# airball_sensor_board_v8_fwd.net
KiCad netlist of a schematic drawn in EAGLE
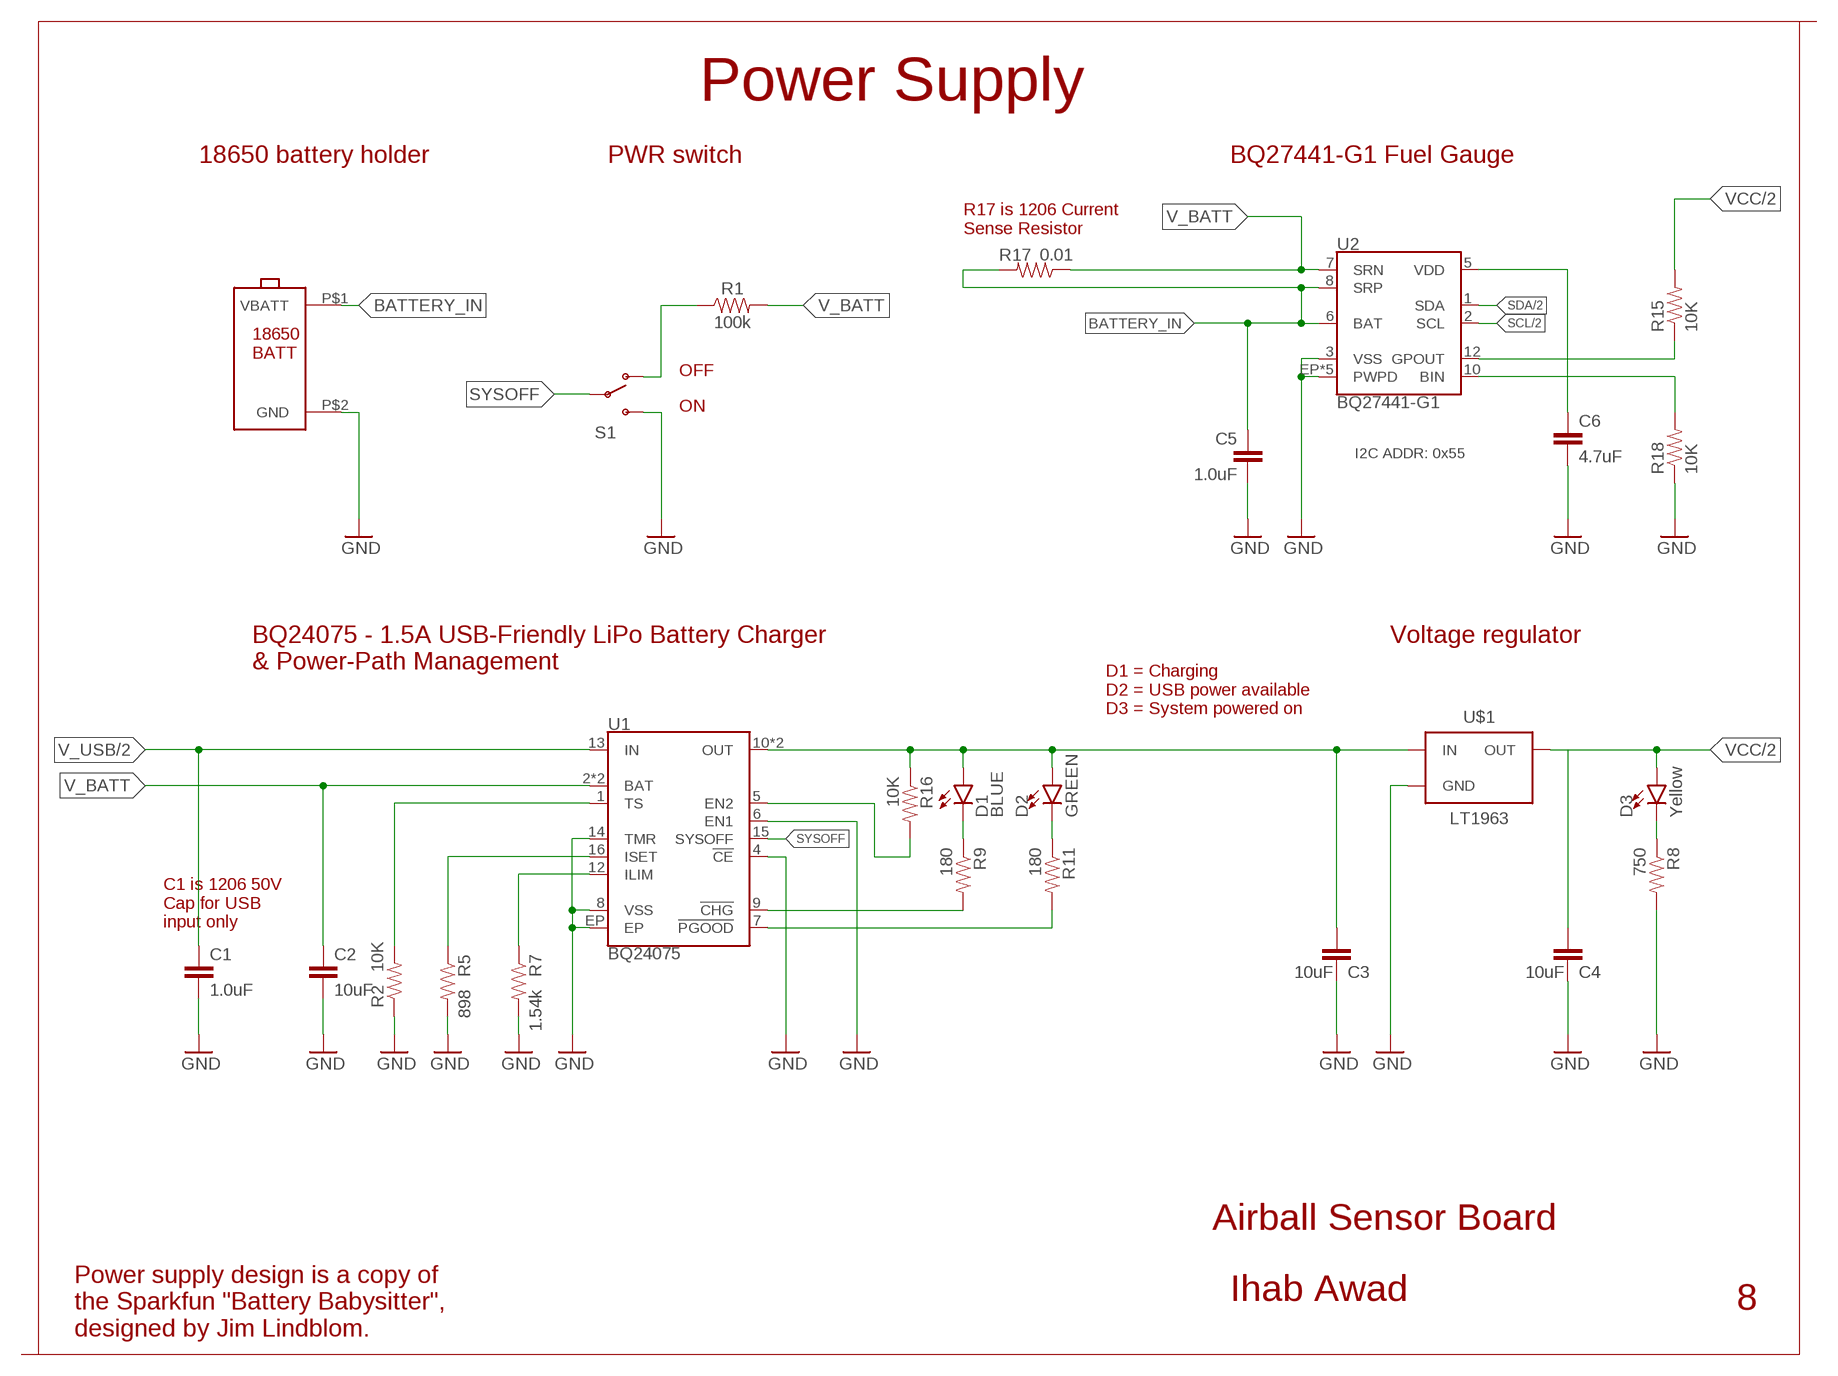
[diagram p0: schematic, sheet 1]
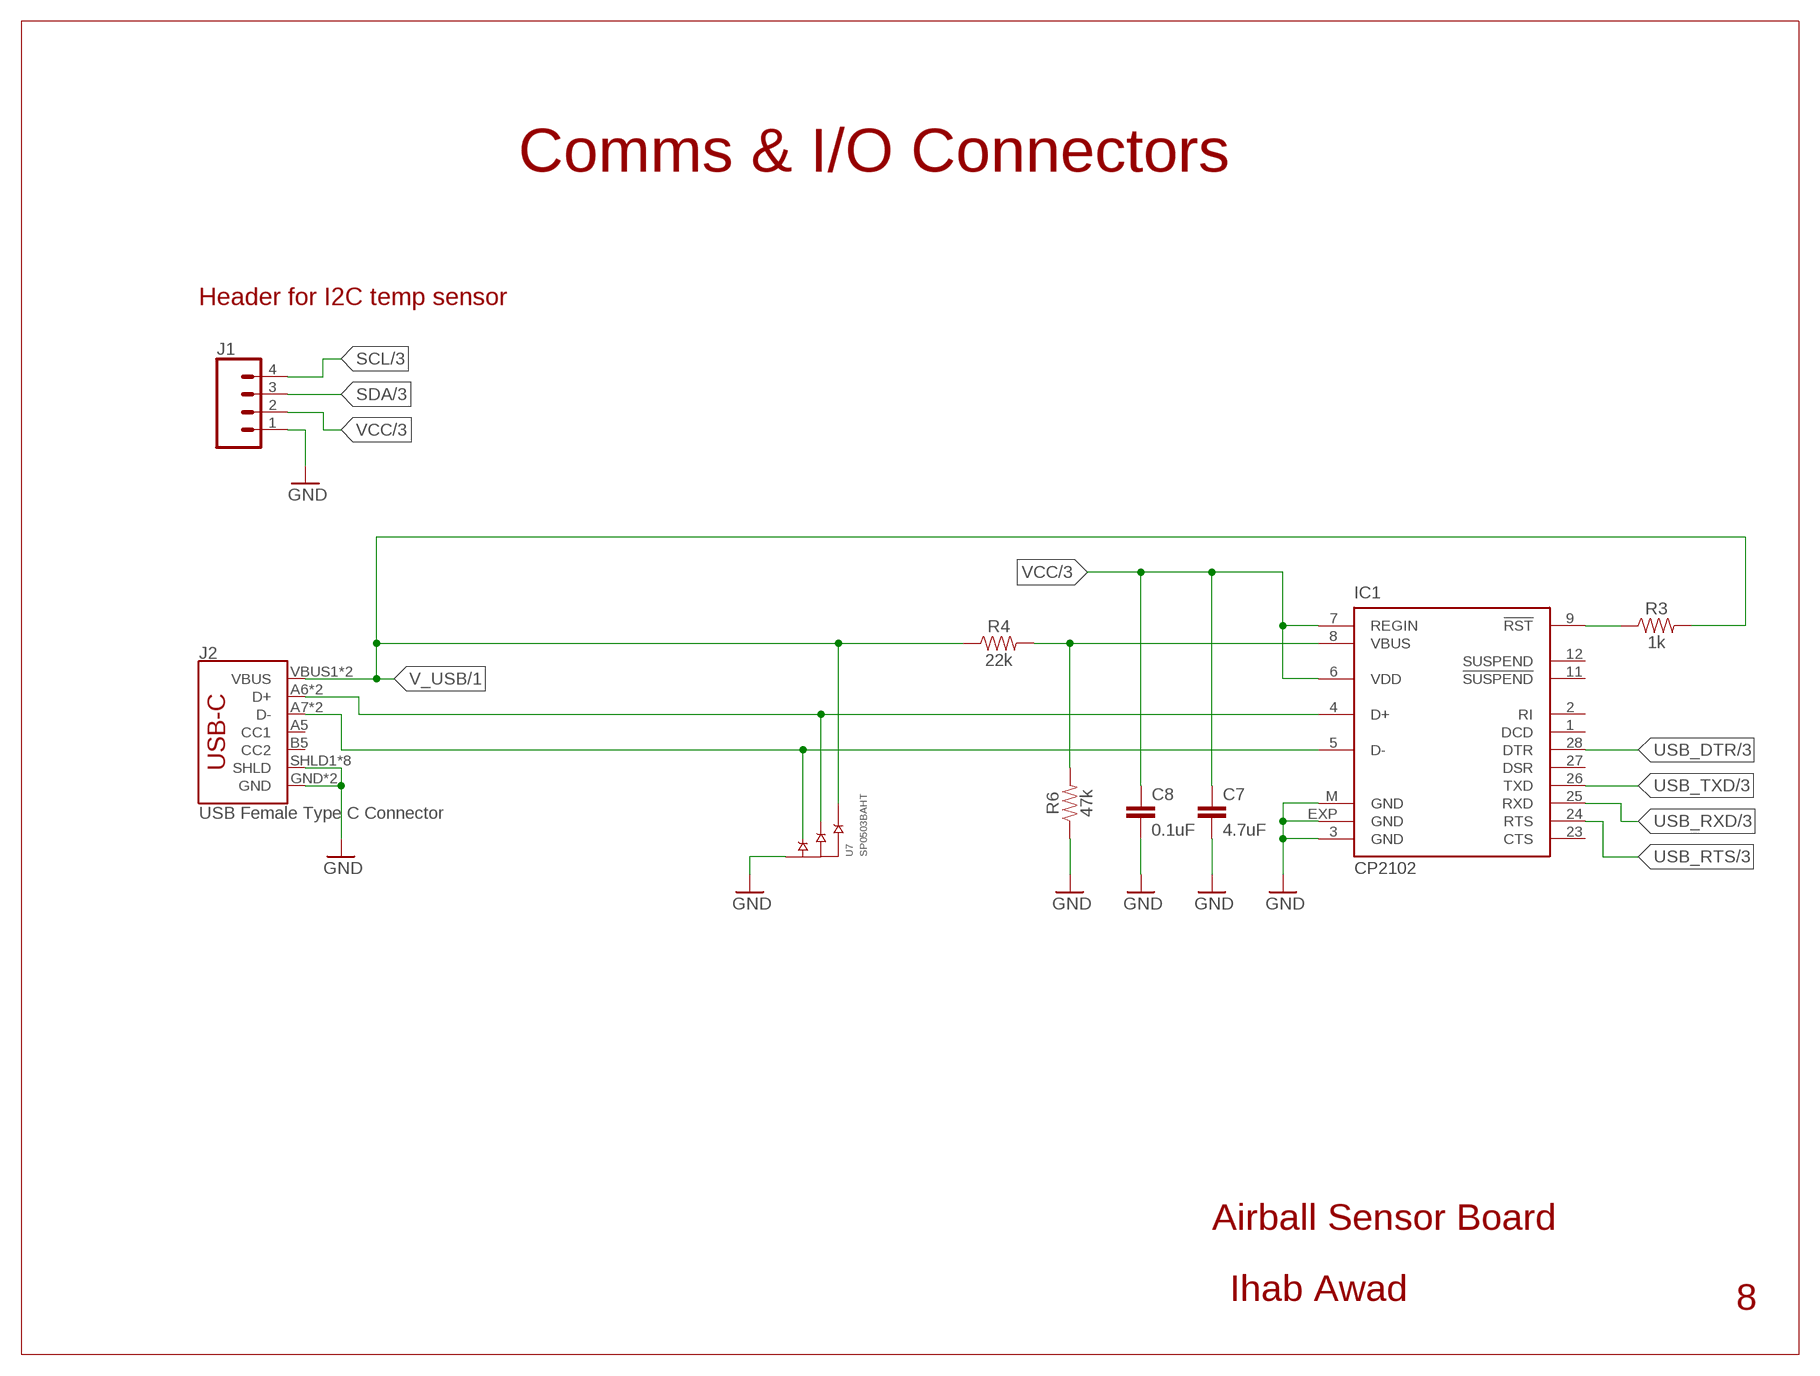
[diagram p1: schematic, sheet 2]
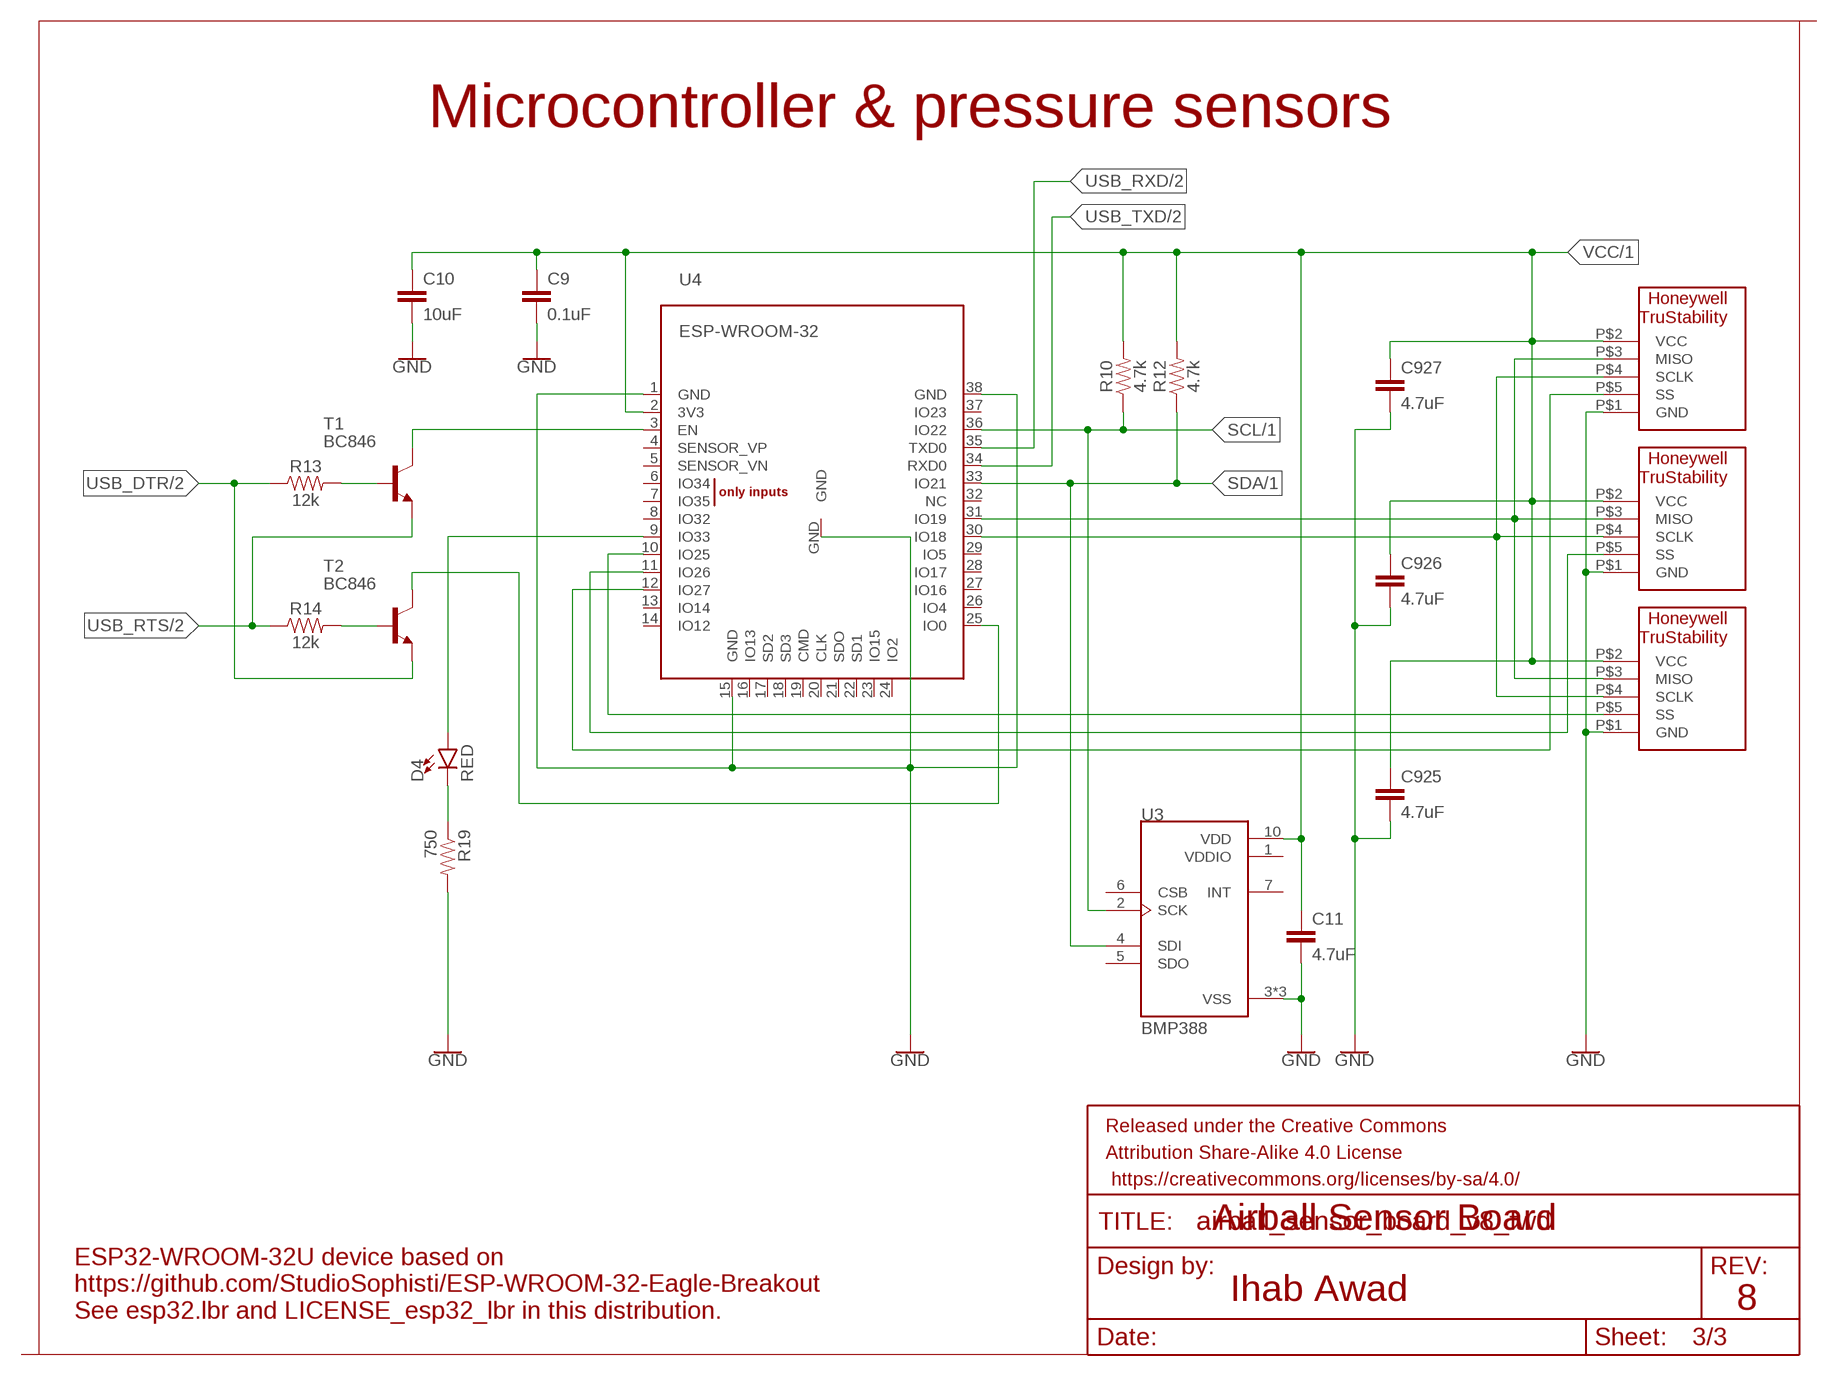
[diagram p2: schematic, sheet 3]

(export (version "E")
  (design (tool "Eeschema 10.0.6"))
  (components
    (comp (ref "C9")
      (value "0.1uF")
      (footprint "eagle-import:0603")
      (libsource (lib "eagle-import") (part "0.1UF-0603-25V-(+80/-20%)"))
    )
    (comp (ref "C10")
      (value "10uF")
      (footprint "eagle-import:0603")
      (libsource (lib "eagle-import") (part "10UF-0603-6.3V-20%"))
    )
    (comp (ref "C11")
      (value "4.7uF")
      (footprint "eagle-import:0603")
      (libsource (lib "eagle-import") (part "4.7UF-0603-6.3V-(10%)"))
    )
    (comp (ref "C925")
      (value "4.7uF")
      (footprint "eagle-import:0603")
      (libsource (lib "eagle-import") (part "4.7UF-0603-6.3V-(10%)"))
    )
    (comp (ref "C926")
      (value "4.7uF")
      (footprint "eagle-import:0603")
      (libsource (lib "eagle-import") (part "4.7UF-0603-6.3V-(10%)"))
    )
    (comp (ref "C927")
      (value "4.7uF")
      (footprint "eagle-import:0603")
      (libsource (lib "eagle-import") (part "4.7UF-0603-6.3V-(10%)"))
    )
    (comp (ref "D4")
      (value "RED")
      (footprint "eagle-import:LED-0603")
      (libsource (lib "eagle-import") (part "LED-RED0603"))
    )
    (comp (ref "FRAME3")
      (value "FRAME-LETTER")
      (footprint "eagle-import:CREATIVE_COMMONS")
      (libsource (lib "eagle-import") (part "FRAME-LETTER"))
    )
    (comp (ref "R10")
      (value "4.7k")
      (footprint "eagle-import:0603")
      (libsource (lib "eagle-import") (part "4.7KOHM-0603-1/10W-1%"))
    )
    (comp (ref "R12")
      (value "4.7k")
      (footprint "eagle-import:0603")
      (libsource (lib "eagle-import") (part "4.7KOHM-0603-1/10W-1%"))
    )
    (comp (ref "R13")
      (value "12k")
      (footprint "eagle-import:0603")
      (libsource (lib "eagle-import") (part "12KOHM-0603-1/10W-1%"))
    )
    (comp (ref "R14")
      (value "12k")
      (footprint "eagle-import:0603")
      (libsource (lib "eagle-import") (part "12KOHM-0603-1/10W-1%"))
    )
    (comp (ref "R19")
      (value "750")
      (footprint "eagle-import:0603-RES")
      (libsource (lib "eagle-import") (part "10KOHM-1/10W-1%(0603)0603"))
    )
    (comp (ref "T1")
      (value "BC846")
      (footprint "eagle-import:SOT23")
      (libsource (lib "eagle-import") (part "BC846"))
    )
    (comp (ref "T2")
      (value "BC846")
      (footprint "eagle-import:SOT23")
      (libsource (lib "eagle-import") (part "BC846"))
    )
    (comp (ref "U$925")
      (value "HONEYWELL_HSC_SMT")
      (footprint "eagle-import:HONEYWELL_HSC_SMT")
      (libsource (lib "eagle-import") (part "HONEYWELL_HSC_SMT"))
    )
    (comp (ref "U$926")
      (value "HONEYWELL_HSC_SMT")
      (footprint "eagle-import:HONEYWELL_HSC_SMT")
      (libsource (lib "eagle-import") (part "HONEYWELL_HSC_SMT"))
    )
    (comp (ref "U$927")
      (value "HONEYWELL_HSC_SMT")
      (footprint "eagle-import:HONEYWELL_HSC_SMT")
      (libsource (lib "eagle-import") (part "HONEYWELL_HSC_SMT"))
    )
    (comp (ref "U3")
      (value "BMP388")
      (footprint "eagle-import:PQFN50P200X200X80-10N")
      (fields (field (name "MF") "Bosch Sensortec"))
      (libsource (lib "eagle-import") (part "BMP388"))
    )
    (comp (ref "U4")
      (value "ESP-WROOM-32")
      (footprint "eagle-import:ESP-WROOM-32")
      (libsource (lib "eagle-import") (part "ESP-WROOM-32"))
    )
    (comp (ref "C7")
      (value "4.7uF")
      (footprint "eagle-import:0603")
      (libsource (lib "eagle-import") (part "4.7UF-0603-35V-(20%)"))
    )
    (comp (ref "C8")
      (value "0.1uF")
      (footprint "eagle-import:0603")
      (libsource (lib "eagle-import") (part "0.1UF-0603-25V-(+80/-20%)"))
    )
    (comp (ref "IC1")
      (value "CP2102")
      (footprint "eagle-import:MLP28")
      (fields (field (name "MF") "FARNELL") (field (name "MPN") "CP2102-GM"))
      (libsource (lib "eagle-import") (part "CP2102"))
    )
    (comp (ref "J1")
      (value "CONN_04JST-PTH")
      (footprint "eagle-import:JST-4-PTH")
      (libsource (lib "eagle-import") (part "CONN_04JST-PTH"))
    )
    (comp (ref "J2")
      (value "USB Female Type C Connector")
      (footprint "eagle-import:USB-C-16P")
      (libsource (lib "eagle-import") (part "USB_C"))
    )
    (comp (ref "R3")
      (value "1k")
      (footprint "eagle-import:0603")
      (libsource (lib "eagle-import") (part "1KOHM-0603-1/10W-1%"))
    )
    (comp (ref "R4")
      (value "22k")
      (footprint "eagle-import:0603")
      (libsource (lib "eagle-import") (part "22KOHM-0603-1/10W-1%"))
    )
    (comp (ref "R6")
      (value "47k")
      (footprint "eagle-import:0603")
      (libsource (lib "eagle-import") (part "47KOHM-0603-1/10W-1%"))
    )
    (comp (ref "U7")
      (value "SP0503BAHT")
      (footprint "eagle-import:SOT143")
      (fields (field (name "DIGI-KEY_PART_NUMBER") "F2715TR-ND") (field (name "MF") "Littelfuse Inc."))
      (libsource (lib "eagle-import") (part "SP0503BAHT"))
    )
    (comp (ref "C1")
      (value "1.0uF")
      (footprint "eagle-import:1206-CAP")
      (libsource (lib "eagle-import") (part "1.0UF50V10%(1206)"))
    )
    (comp (ref "C2")
      (value "10uF")
      (footprint "eagle-import:0805-CAP")
      (libsource (lib "eagle-import") (part "10UF10V10%(0805)"))
    )
    (comp (ref "C3")
      (value "10uF")
      (footprint "eagle-import:0805-CAP")
      (libsource (lib "eagle-import") (part "10UF10V10%(0805)"))
    )
    (comp (ref "C4")
      (value "10uF")
      (footprint "eagle-import:0805-CAP")
      (libsource (lib "eagle-import") (part "10UF10V10%(0805)"))
    )
    (comp (ref "C5")
      (value "1.0uF")
      (footprint "eagle-import:0603-CAP")
      (libsource (lib "eagle-import") (part "1.0UF-16V-10%(0603)"))
    )
    (comp (ref "C6")
      (value "4.7uF")
      (footprint "eagle-import:0603")
      (libsource (lib "eagle-import") (part "4.7UF-0603-35V-(20%)"))
    )
    (comp (ref "D1")
      (value "BLUE")
      (footprint "eagle-import:LED-0603")
      (libsource (lib "eagle-import") (part "LED-BLUE0603"))
    )
    (comp (ref "D2")
      (value "GREEN")
      (footprint "eagle-import:LED-0603")
      (libsource (lib "eagle-import") (part "LED-GREEN0603"))
    )
    (comp (ref "D3")
      (value "Yellow")
      (footprint "eagle-import:LED-0603")
      (libsource (lib "eagle-import") (part "LED-YELLOW0603"))
    )
    (comp (ref "R1")
      (value "100k")
      (footprint "eagle-import:0603")
      (libsource (lib "eagle-import") (part "100KOHM-0603-1/10W-1%"))
    )
    (comp (ref "R2")
      (value "10K")
      (footprint "eagle-import:0603-RES")
      (libsource (lib "eagle-import") (part "10KOHM-1/10W-1%(0603)0603"))
    )
    (comp (ref "R5")
      (value "898")
      (footprint "eagle-import:0603-RES")
      (libsource (lib "eagle-import") (part "RESISTOR0603-RES"))
    )
    (comp (ref "R7")
      (value "1.54k")
      (footprint "eagle-import:0603-RES")
      (libsource (lib "eagle-import") (part "RESISTOR0603-RES"))
    )
    (comp (ref "R8")
      (value "750")
      (footprint "eagle-import:0603-RES")
      (libsource (lib "eagle-import") (part "10KOHM-1/10W-1%(0603)0603"))
    )
    (comp (ref "R9")
      (value "180")
      (footprint "eagle-import:0603-RES")
      (libsource (lib "eagle-import") (part "180OHM1/10W1%(0603)"))
    )
    (comp (ref "R11")
      (value "180")
      (footprint "eagle-import:0603-RES")
      (libsource (lib "eagle-import") (part "180OHM1/10W1%(0603)"))
    )
    (comp (ref "R15")
      (value "10K")
      (footprint "eagle-import:0603-RES")
      (libsource (lib "eagle-import") (part "10KOHM-1/10W-1%(0603)0603"))
    )
    (comp (ref "R16")
      (value "10K")
      (footprint "eagle-import:0603-RES")
      (libsource (lib "eagle-import") (part "10KOHM-1/10W-1%(0603)0603"))
    )
    (comp (ref "R17")
      (value "0.01")
      (footprint "eagle-import:1206")
      (libsource (lib "eagle-import") (part "SparkFun-Resistors_RESISTOR1206"))
    )
    (comp (ref "R18")
      (value "10K")
      (footprint "eagle-import:0603-RES")
      (libsource (lib "eagle-import") (part "10KOHM-1/10W-1%(0603)0603"))
    )
    (comp (ref "S1")
      (value "SWITCH-SPDTSMD")
      (footprint "eagle-import:SWITCH_SPDT_SMD")
      (libsource (lib "eagle-import") (part "SWITCH-SPDTSMD"))
    )
    (comp (ref "U$1")
      (value "LT1963")
      (footprint "eagle-import:SOT223-3")
      (libsource (lib "eagle-import") (part "LT1963"))
    )
    (comp (ref "U$2")
      (value "KEYSTONE_1042P_18650_BATT_HOLDER")
      (footprint "eagle-import:KEYSTONE_1042P_18650_BATT_HOLDER")
      (libsource (lib "eagle-import") (part "KEYSTONE_1042P_18650_BATT_HOLDER"))
    )
    (comp (ref "U1")
      (value "BQ24075")
      (footprint "eagle-import:PVQFN-N16")
      (libsource (lib "eagle-import") (part "BQ24075"))
    )
    (comp (ref "U2")
      (value "BQ27441-G1")
      (footprint "eagle-import:PDSO-N12")
      (libsource (lib "eagle-import") (part "BQ27441-G1"))
    )
  )
  (nets
    (net (code "1") (name "BATTERY_IN") (class "Default")
      (node (ref "C5") (pin "1") (pinfunction "1_1") (pintype "passive"))
      (node (ref "R17") (pin "2") (pinfunction "2_2") (pintype "passive"))
      (node (ref "U$2") (pin "P$1") (pinfunction "VBATT_P$1") (pintype "bidirectional"))
      (node (ref "U2") (pin "6") (pinfunction "BAT_6") (pintype "bidirectional"))
      (node (ref "U2") (pin "8") (pinfunction "SRP_8") (pintype "bidirectional"))
    )
    (net (code "2") (name "GND") (class "Default")
      (node (ref "C1") (pin "2") (pinfunction "2_2") (pintype "passive"))
      (node (ref "C10") (pin "2") (pinfunction "2_2") (pintype "passive"))
      (node (ref "C11") (pin "2") (pinfunction "2_2") (pintype "passive"))
      (node (ref "C2") (pin "2") (pinfunction "2_2") (pintype "passive"))
      (node (ref "C3") (pin "2") (pinfunction "2_2") (pintype "passive"))
      (node (ref "C4") (pin "2") (pinfunction "2_2") (pintype "passive"))
      (node (ref "C5") (pin "2") (pinfunction "2_2") (pintype "passive"))
      (node (ref "C6") (pin "2") (pinfunction "2_2") (pintype "passive"))
      (node (ref "C7") (pin "2") (pinfunction "2_2") (pintype "passive"))
      (node (ref "C8") (pin "2") (pinfunction "2_2") (pintype "passive"))
      (node (ref "C9") (pin "2") (pinfunction "2_2") (pintype "passive"))
      (node (ref "C925") (pin "2") (pinfunction "2_2") (pintype "passive"))
      (node (ref "C926") (pin "2") (pinfunction "2_2") (pintype "passive"))
      (node (ref "C927") (pin "2") (pinfunction "2_2") (pintype "passive"))
      (node (ref "IC1") (pin "3") (pinfunction "GND_3") (pintype "power_in"))
      (node (ref "IC1") (pin "EXP") (pinfunction "GND_EXP") (pintype "power_in"))
      (node (ref "IC1") (pin "M") (pinfunction "GND_M") (pintype "power_in"))
      (node (ref "J1") (pin "1") (pinfunction "1_1") (pintype "passive"))
      (node (ref "J2") (pin "GND") (pinfunction "GND_GND") (pintype "bidirectional"))
      (node (ref "J2") (pin "GND2") (pinfunction "GND_GND2") (pintype "bidirectional"))
      (node (ref "J2") (pin "SHLD1") (pinfunction "SHLD_SHLD1") (pintype "bidirectional"))
      (node (ref "J2") (pin "SHLD2") (pinfunction "SHLD_SHLD2") (pintype "bidirectional"))
      (node (ref "J2") (pin "SHLD3") (pinfunction "SHLD_SHLD3") (pintype "bidirectional"))
      (node (ref "J2") (pin "SHLD4") (pinfunction "SHLD_SHLD4") (pintype "bidirectional"))
      (node (ref "J2") (pin "SHLD5") (pinfunction "SHLD_SHLD5") (pintype "bidirectional"))
      (node (ref "J2") (pin "SHLD6") (pinfunction "SHLD_SHLD6") (pintype "bidirectional"))
      (node (ref "J2") (pin "SHLD7") (pinfunction "SHLD_SHLD7") (pintype "bidirectional"))
      (node (ref "J2") (pin "SHLD8") (pinfunction "SHLD_SHLD8") (pintype "bidirectional"))
      (node (ref "R18") (pin "1") (pinfunction "1_1") (pintype "passive"))
      (node (ref "R19") (pin "2") (pinfunction "2_2") (pintype "passive"))
      (node (ref "R2") (pin "1") (pinfunction "1_1") (pintype "passive"))
      (node (ref "R5") (pin "2") (pinfunction "2_2") (pintype "passive"))
      (node (ref "R6") (pin "1") (pinfunction "1_1") (pintype "passive"))
      (node (ref "R7") (pin "2") (pinfunction "2_2") (pintype "passive"))
      (node (ref "R8") (pin "2") (pinfunction "2_2") (pintype "passive"))
      (node (ref "S1") (pin "3") (pinfunction "S_3") (pintype "passive"))
      (node (ref "U$1") (pin "2") (pinfunction "GND_2") (pintype "power_in"))
      (node (ref "U$1") (pin "TAB") (pinfunction "GND_TAB") (pintype "power_in"))
      (node (ref "U$2") (pin "P$2") (pinfunction "GND_P$2") (pintype "bidirectional"))
      (node (ref "U$925") (pin "P$1") (pinfunction "GND_P$1") (pintype "bidirectional"))
      (node (ref "U$926") (pin "P$1") (pinfunction "GND_P$1") (pintype "bidirectional"))
      (node (ref "U$927") (pin "P$1") (pinfunction "GND_P$1") (pintype "bidirectional"))
      (node (ref "U1") (pin "14") (pinfunction "TMR_14") (pintype "bidirectional"))
      (node (ref "U1") (pin "4") (pinfunction "~{CE}_4") (pintype "bidirectional"))
      (node (ref "U1") (pin "6") (pinfunction "EN1_6") (pintype "bidirectional"))
      (node (ref "U1") (pin "8") (pinfunction "VSS_8") (pintype "bidirectional"))
      (node (ref "U1") (pin "EP") (pinfunction "EP_EP") (pintype "bidirectional"))
      (node (ref "U2") (pin "3") (pinfunction "VSS_3") (pintype "bidirectional"))
      (node (ref "U2") (pin "EP") (pinfunction "PWPD_EP") (pintype "bidirectional"))
      (node (ref "U2") (pin "EP1") (pinfunction "PWPD_EP1") (pintype "bidirectional"))
      (node (ref "U2") (pin "EP2") (pinfunction "PWPD_EP2") (pintype "bidirectional"))
      (node (ref "U2") (pin "EP3") (pinfunction "PWPD_EP3") (pintype "bidirectional"))
      (node (ref "U2") (pin "EP4") (pinfunction "PWPD_EP4") (pintype "bidirectional"))
      (node (ref "U3") (pin "3") (pinfunction "VSS_3") (pintype "power_in"))
      (node (ref "U3") (pin "8") (pinfunction "VSS_8") (pintype "power_in"))
      (node (ref "U3") (pin "9") (pinfunction "VSS_9") (pintype "power_in"))
      (node (ref "U4") (pin "1") (pinfunction "GND_1") (pintype "bidirectional"))
      (node (ref "U4") (pin "15") (pinfunction "GND_15") (pintype "bidirectional"))
      (node (ref "U4") (pin "38") (pinfunction "GND_38") (pintype "bidirectional"))
      (node (ref "U4") (pin "GND") (pinfunction "GND_GND") (pintype "bidirectional"))
      (node (ref "U7") (pin "1") (pinfunction "GND_1") (pintype "bidirectional"))
    )
    (net (code "3") (name "Net-(D1-PadC)") (class "Default")
      (node (ref "D1") (pin "C") (pinfunction "C_C") (pintype "passive"))
      (node (ref "R9") (pin "1") (pinfunction "1_1") (pintype "passive"))
    )
    (net (code "4") (name "Net-(D2-PadC)") (class "Default")
      (node (ref "D2") (pin "C") (pinfunction "C_C") (pintype "passive"))
      (node (ref "R11") (pin "1") (pinfunction "1_1") (pintype "passive"))
    )
    (net (code "5") (name "Net-(D3-PadC)") (class "Default")
      (node (ref "D3") (pin "C") (pinfunction "C_C") (pintype "passive"))
      (node (ref "R8") (pin "1") (pinfunction "1_1") (pintype "passive"))
    )
    (net (code "6") (name "Net-(D4-PadC)") (class "Default")
      (node (ref "D4") (pin "C") (pinfunction "C_C") (pintype "passive"))
      (node (ref "R19") (pin "1") (pinfunction "1_1") (pintype "passive"))
    )
    (net (code "7") (name "Net-(IC1-D+)") (class "Default")
      (node (ref "IC1") (pin "4") (pinfunction "D+_4") (pintype "bidirectional"))
      (node (ref "J2") (pin "A6") (pinfunction "D+_A6") (pintype "bidirectional"))
      (node (ref "J2") (pin "B6") (pinfunction "D+_B6") (pintype "bidirectional"))
      (node (ref "U7") (pin "3") (pinfunction "B_3") (pintype "bidirectional"))
    )
    (net (code "8") (name "Net-(IC1-D-)") (class "Default")
      (node (ref "IC1") (pin "5") (pinfunction "D-_5") (pintype "bidirectional"))
      (node (ref "J2") (pin "A7") (pinfunction "D-_A7") (pintype "bidirectional"))
      (node (ref "J2") (pin "B7") (pinfunction "D-_B7") (pintype "bidirectional"))
      (node (ref "U7") (pin "2") (pinfunction "A_2") (pintype "bidirectional"))
    )
    (net (code "9") (name "Net-(IC1-VBUS)") (class "Default")
      (node (ref "IC1") (pin "8") (pinfunction "VBUS_8") (pintype "input"))
      (node (ref "R4") (pin "2") (pinfunction "2_2") (pintype "passive"))
      (node (ref "R6") (pin "2") (pinfunction "2_2") (pintype "passive"))
    )
    (net (code "10") (name "Net-(IC1-~{RST})") (class "Default")
      (node (ref "IC1") (pin "9") (pinfunction "~{RST}_9") (pintype "bidirectional"))
      (node (ref "R3") (pin "1") (pinfunction "1_1") (pintype "passive"))
    )
    (net (code "11") (name "Net-(S1-O)") (class "Default")
      (node (ref "R1") (pin "1") (pinfunction "1_1") (pintype "passive"))
      (node (ref "S1") (pin "1") (pinfunction "O_1") (pintype "passive"))
    )
    (net (code "12") (name "Net-(T1-B)") (class "Default")
      (node (ref "R13") (pin "2") (pinfunction "2_2") (pintype "passive"))
      (node (ref "T1") (pin "1") (pinfunction "B_1") (pintype "passive"))
    )
    (net (code "13") (name "Net-(T1-C)") (class "Default")
      (node (ref "T1") (pin "3") (pinfunction "C_3") (pintype "passive"))
      (node (ref "U4") (pin "3") (pinfunction "EN_3") (pintype "bidirectional"))
    )
    (net (code "14") (name "Net-(T2-B)") (class "Default")
      (node (ref "R14") (pin "2") (pinfunction "2_2") (pintype "passive"))
      (node (ref "T2") (pin "1") (pinfunction "B_1") (pintype "passive"))
    )
    (net (code "15") (name "Net-(T2-C)") (class "Default")
      (node (ref "T2") (pin "3") (pinfunction "C_3") (pintype "passive"))
      (node (ref "U4") (pin "25") (pinfunction "IO0_25") (pintype "bidirectional"))
    )
    (net (code "16") (name "Net-(U$1-IN)") (class "Default")
      (node (ref "C3") (pin "1") (pinfunction "1_1") (pintype "passive"))
      (node (ref "D1") (pin "A") (pinfunction "A_A") (pintype "passive"))
      (node (ref "D2") (pin "A") (pinfunction "A_A") (pintype "passive"))
      (node (ref "R16") (pin "1") (pinfunction "1_1") (pintype "passive"))
      (node (ref "U$1") (pin "1") (pinfunction "IN_1") (pintype "power_in"))
      (node (ref "U1") (pin "10") (pinfunction "OUT_10") (pintype "bidirectional"))
      (node (ref "U1") (pin "11") (pinfunction "OUT_11") (pintype "bidirectional"))
    )
    (net (code "17") (name "Net-(U$925-MISO)") (class "Default")
      (node (ref "U$925") (pin "P$3") (pinfunction "MISO_P$3") (pintype "bidirectional"))
      (node (ref "U$926") (pin "P$3") (pinfunction "MISO_P$3") (pintype "bidirectional"))
      (node (ref "U$927") (pin "P$3") (pinfunction "MISO_P$3") (pintype "bidirectional"))
      (node (ref "U4") (pin "31") (pinfunction "IO19_31") (pintype "bidirectional"))
    )
    (net (code "18") (name "Net-(U$925-SCLK)") (class "Default")
      (node (ref "U$925") (pin "P$4") (pinfunction "SCLK_P$4") (pintype "bidirectional"))
      (node (ref "U$926") (pin "P$4") (pinfunction "SCLK_P$4") (pintype "bidirectional"))
      (node (ref "U$927") (pin "P$4") (pinfunction "SCLK_P$4") (pintype "bidirectional"))
      (node (ref "U4") (pin "30") (pinfunction "IO18_30") (pintype "bidirectional"))
    )
    (net (code "19") (name "Net-(U$925-SS)") (class "Default")
      (node (ref "U$925") (pin "P$5") (pinfunction "SS_P$5") (pintype "bidirectional"))
      (node (ref "U4") (pin "10") (pinfunction "IO25_10") (pintype "bidirectional"))
    )
    (net (code "20") (name "Net-(U$926-SS)") (class "Default")
      (node (ref "U$926") (pin "P$5") (pinfunction "SS_P$5") (pintype "bidirectional"))
      (node (ref "U4") (pin "11") (pinfunction "IO26_11") (pintype "bidirectional"))
    )
    (net (code "21") (name "Net-(U$927-SS)") (class "Default")
      (node (ref "U$927") (pin "P$5") (pinfunction "SS_P$5") (pintype "bidirectional"))
      (node (ref "U4") (pin "12") (pinfunction "IO27_12") (pintype "bidirectional"))
    )
    (net (code "22") (name "Net-(U1-EN2)") (class "Default")
      (node (ref "R16") (pin "2") (pinfunction "2_2") (pintype "passive"))
      (node (ref "U1") (pin "5") (pinfunction "EN2_5") (pintype "bidirectional"))
    )
    (net (code "23") (name "Net-(U1-ILIM)") (class "Default")
      (node (ref "R7") (pin "1") (pinfunction "1_1") (pintype "passive"))
      (node (ref "U1") (pin "12") (pinfunction "ILIM_12") (pintype "bidirectional"))
    )
    (net (code "24") (name "Net-(U1-ISET)") (class "Default")
      (node (ref "R5") (pin "1") (pinfunction "1_1") (pintype "passive"))
      (node (ref "U1") (pin "16") (pinfunction "ISET_16") (pintype "bidirectional"))
    )
    (net (code "25") (name "Net-(U1-TS)") (class "Default")
      (node (ref "R2") (pin "2") (pinfunction "2_2") (pintype "passive"))
      (node (ref "U1") (pin "1") (pinfunction "TS_1") (pintype "bidirectional"))
    )
    (net (code "26") (name "Net-(U1-~{CHG})") (class "Default")
      (node (ref "R9") (pin "2") (pinfunction "2_2") (pintype "passive"))
      (node (ref "U1") (pin "9") (pinfunction "~{CHG}_9") (pintype "bidirectional"))
    )
    (net (code "27") (name "Net-(U1-~{PGOOD})") (class "Default")
      (node (ref "R11") (pin "2") (pinfunction "2_2") (pintype "passive"))
      (node (ref "U1") (pin "7") (pinfunction "~{PGOOD}_7") (pintype "bidirectional"))
    )
    (net (code "28") (name "Net-(U2-BIN)") (class "Default")
      (node (ref "R18") (pin "2") (pinfunction "2_2") (pintype "passive"))
      (node (ref "U2") (pin "10") (pinfunction "BIN_10") (pintype "bidirectional"))
    )
    (net (code "29") (name "Net-(U2-GPOUT)") (class "Default")
      (node (ref "R15") (pin "1") (pinfunction "1_1") (pintype "passive"))
      (node (ref "U2") (pin "12") (pinfunction "GPOUT_12") (pintype "bidirectional"))
    )
    (net (code "30") (name "Net-(U2-VDD)") (class "Default")
      (node (ref "C6") (pin "1") (pinfunction "1_1") (pintype "passive"))
      (node (ref "U2") (pin "5") (pinfunction "VDD_5") (pintype "bidirectional"))
    )
    (net (code "31") (name "Net-(U4-IO33)") (class "Default")
      (node (ref "D4") (pin "A") (pinfunction "A_A") (pintype "passive"))
      (node (ref "U4") (pin "9") (pinfunction "IO33_9") (pintype "bidirectional"))
    )
    (net (code "32") (name "SCL") (class "Default")
      (node (ref "J1") (pin "4") (pinfunction "4_4") (pintype "passive"))
      (node (ref "R10") (pin "1") (pinfunction "1_1") (pintype "passive"))
      (node (ref "U2") (pin "2") (pinfunction "SCL_2") (pintype "bidirectional"))
      (node (ref "U3") (pin "2") (pinfunction "SCK_2") (pintype "input"))
      (node (ref "U4") (pin "36") (pinfunction "IO22_36") (pintype "bidirectional"))
    )
    (net (code "33") (name "SDA") (class "Default")
      (node (ref "J1") (pin "3") (pinfunction "3_3") (pintype "passive"))
      (node (ref "R12") (pin "1") (pinfunction "1_1") (pintype "passive"))
      (node (ref "U2") (pin "1") (pinfunction "SDA_1") (pintype "bidirectional"))
      (node (ref "U3") (pin "4") (pinfunction "SDI_4") (pintype "bidirectional"))
      (node (ref "U4") (pin "33") (pinfunction "IO21_33") (pintype "bidirectional"))
    )
    (net (code "34") (name "SYSOFF") (class "Default")
      (node (ref "S1") (pin "2") (pinfunction "P_2") (pintype "passive"))
      (node (ref "U1") (pin "15") (pinfunction "SYSOFF_15") (pintype "bidirectional"))
    )
    (net (code "35") (name "USB_DTR") (class "Default")
      (node (ref "IC1") (pin "28") (pinfunction "DTR_28") (pintype "output"))
      (node (ref "R13") (pin "1") (pinfunction "1_1") (pintype "passive"))
      (node (ref "T2") (pin "2") (pinfunction "E_2") (pintype "passive"))
    )
    (net (code "36") (name "USB_RTS") (class "Default")
      (node (ref "IC1") (pin "24") (pinfunction "RTS_24") (pintype "output"))
      (node (ref "R14") (pin "1") (pinfunction "1_1") (pintype "passive"))
      (node (ref "T1") (pin "2") (pinfunction "E_2") (pintype "passive"))
    )
    (net (code "37") (name "USB_RXD") (class "Default")
      (node (ref "IC1") (pin "25") (pinfunction "RXD_25") (pintype "input"))
      (node (ref "U4") (pin "35") (pinfunction "TXD0_35") (pintype "bidirectional"))
    )
    (net (code "38") (name "USB_TXD") (class "Default")
      (node (ref "IC1") (pin "26") (pinfunction "TXD_26") (pintype "output"))
      (node (ref "U4") (pin "34") (pinfunction "RXD0_34") (pintype "bidirectional"))
    )
    (net (code "39") (name "VCC") (class "Default")
      (node (ref "C10") (pin "1") (pinfunction "1_1") (pintype "passive"))
      (node (ref "C11") (pin "1") (pinfunction "1_1") (pintype "passive"))
      (node (ref "C4") (pin "1") (pinfunction "1_1") (pintype "passive"))
      (node (ref "C7") (pin "1") (pinfunction "1_1") (pintype "passive"))
      (node (ref "C8") (pin "1") (pinfunction "1_1") (pintype "passive"))
      (node (ref "C9") (pin "1") (pinfunction "1_1") (pintype "passive"))
      (node (ref "C925") (pin "1") (pinfunction "1_1") (pintype "passive"))
      (node (ref "C926") (pin "1") (pinfunction "1_1") (pintype "passive"))
      (node (ref "C927") (pin "1") (pinfunction "1_1") (pintype "passive"))
      (node (ref "D3") (pin "A") (pinfunction "A_A") (pintype "passive"))
      (node (ref "IC1") (pin "6") (pinfunction "VDD_6") (pintype "power_in"))
      (node (ref "IC1") (pin "7") (pinfunction "REGIN_7") (pintype "passive"))
      (node (ref "J1") (pin "2") (pinfunction "2_2") (pintype "passive"))
      (node (ref "R10") (pin "2") (pinfunction "2_2") (pintype "passive"))
      (node (ref "R12") (pin "2") (pinfunction "2_2") (pintype "passive"))
      (node (ref "R15") (pin "2") (pinfunction "2_2") (pintype "passive"))
      (node (ref "U$1") (pin "3") (pinfunction "OUT_3") (pintype "power_in"))
      (node (ref "U$925") (pin "P$2") (pinfunction "VCC_P$2") (pintype "bidirectional"))
      (node (ref "U$926") (pin "P$2") (pinfunction "VCC_P$2") (pintype "bidirectional"))
      (node (ref "U$927") (pin "P$2") (pinfunction "VCC_P$2") (pintype "bidirectional"))
      (node (ref "U3") (pin "10") (pinfunction "VDD_10") (pintype "power_in"))
      (node (ref "U4") (pin "2") (pinfunction "3V3_2") (pintype "bidirectional"))
    )
    (net (code "40") (name "VDDIO") (class "Default")
      (node (ref "U3") (pin "1") (pinfunction "VDDIO_1") (pintype "power_in"))
    )
    (net (code "41") (name "V_BATT") (class "Default")
      (node (ref "C2") (pin "1") (pinfunction "1_1") (pintype "passive"))
      (node (ref "R1") (pin "2") (pinfunction "2_2") (pintype "passive"))
      (node (ref "R17") (pin "1") (pinfunction "1_1") (pintype "passive"))
      (node (ref "U1") (pin "2") (pinfunction "BAT_2") (pintype "bidirectional"))
      (node (ref "U1") (pin "3") (pinfunction "BAT_3") (pintype "bidirectional"))
      (node (ref "U2") (pin "7") (pinfunction "SRN_7") (pintype "bidirectional"))
    )
    (net (code "42") (name "V_USB") (class "Default")
      (node (ref "C1") (pin "1") (pinfunction "1_1") (pintype "passive"))
      (node (ref "J2") (pin "VBUS1") (pinfunction "VBUS_VBUS1") (pintype "bidirectional"))
      (node (ref "J2") (pin "VBUS2") (pinfunction "VBUS_VBUS2") (pintype "bidirectional"))
      (node (ref "R3") (pin "2") (pinfunction "2_2") (pintype "passive"))
      (node (ref "R4") (pin "1") (pinfunction "1_1") (pintype "passive"))
      (node (ref "U1") (pin "13") (pinfunction "IN_13") (pintype "bidirectional"))
      (node (ref "U7") (pin "4") (pinfunction "C_4") (pintype "bidirectional"))
    )
    (net (code "43") (name "unconnected-(IC1-CTS-Pad23)") (class "Default")
      (node (ref "IC1") (pin "23") (pinfunction "CTS_23") (pintype "input"))
    )
    (net (code "44") (name "unconnected-(IC1-DCD-Pad1)") (class "Default")
      (node (ref "IC1") (pin "1") (pinfunction "DCD_1") (pintype "input"))
    )
    (net (code "45") (name "unconnected-(IC1-DSR-Pad27)") (class "Default")
      (node (ref "IC1") (pin "27") (pinfunction "DSR_27") (pintype "input"))
    )
    (net (code "46") (name "unconnected-(IC1-RI-Pad2)") (class "Default")
      (node (ref "IC1") (pin "2") (pinfunction "RI_2") (pintype "input"))
    )
    (net (code "47") (name "unconnected-(IC1-SUSPEND-Pad12)") (class "Default")
      (node (ref "IC1") (pin "12") (pinfunction "SUSPEND_12") (pintype "output"))
    )
    (net (code "48") (name "unconnected-(IC1-~{SUSPEND}-Pad11)") (class "Default")
      (node (ref "IC1") (pin "11") (pinfunction "~{SUSPEND}_11") (pintype "output"))
    )
    (net (code "49") (name "unconnected-(J2-CC1-PadA5)") (class "Default")
      (node (ref "J2") (pin "A5") (pinfunction "CC1_A5") (pintype "bidirectional"))
    )
    (net (code "50") (name "unconnected-(J2-CC2-PadB5)") (class "Default")
      (node (ref "J2") (pin "B5") (pinfunction "CC2_B5") (pintype "bidirectional"))
    )
    (net (code "51") (name "unconnected-(U3-CSB-Pad6)") (class "Default")
      (node (ref "U3") (pin "6") (pinfunction "CSB_6") (pintype "input"))
    )
    (net (code "52") (name "unconnected-(U3-INT-Pad7)") (class "Default")
      (node (ref "U3") (pin "7") (pinfunction "INT_7") (pintype "output"))
    )
    (net (code "53") (name "unconnected-(U3-SDO-Pad5)") (class "Default")
      (node (ref "U3") (pin "5") (pinfunction "SDO_5") (pintype "bidirectional"))
    )
    (net (code "54") (name "unconnected-(U4-CLK-Pad20)") (class "Default")
      (node (ref "U4") (pin "20") (pinfunction "CLK_20") (pintype "bidirectional"))
    )
    (net (code "55") (name "unconnected-(U4-CMD-Pad19)") (class "Default")
      (node (ref "U4") (pin "19") (pinfunction "CMD_19") (pintype "bidirectional"))
    )
    (net (code "56") (name "unconnected-(U4-IO2-Pad24)") (class "Default")
      (node (ref "U4") (pin "24") (pinfunction "IO2_24") (pintype "bidirectional"))
    )
    (net (code "57") (name "unconnected-(U4-IO4-Pad26)") (class "Default")
      (node (ref "U4") (pin "26") (pinfunction "IO4_26") (pintype "bidirectional"))
    )
    (net (code "58") (name "unconnected-(U4-IO5-Pad29)") (class "Default")
      (node (ref "U4") (pin "29") (pinfunction "IO5_29") (pintype "bidirectional"))
    )
    (net (code "59") (name "unconnected-(U4-IO12-Pad14)") (class "Default")
      (node (ref "U4") (pin "14") (pinfunction "IO12_14") (pintype "bidirectional"))
    )
    (net (code "60") (name "unconnected-(U4-IO13-Pad16)") (class "Default")
      (node (ref "U4") (pin "16") (pinfunction "IO13_16") (pintype "bidirectional"))
    )
    (net (code "61") (name "unconnected-(U4-IO14-Pad13)") (class "Default")
      (node (ref "U4") (pin "13") (pinfunction "IO14_13") (pintype "bidirectional"))
    )
    (net (code "62") (name "unconnected-(U4-IO15-Pad23)") (class "Default")
      (node (ref "U4") (pin "23") (pinfunction "IO15_23") (pintype "bidirectional"))
    )
    (net (code "63") (name "unconnected-(U4-IO16-Pad27)") (class "Default")
      (node (ref "U4") (pin "27") (pinfunction "IO16_27") (pintype "bidirectional"))
    )
    (net (code "64") (name "unconnected-(U4-IO17-Pad28)") (class "Default")
      (node (ref "U4") (pin "28") (pinfunction "IO17_28") (pintype "bidirectional"))
    )
    (net (code "65") (name "unconnected-(U4-IO23-Pad37)") (class "Default")
      (node (ref "U4") (pin "37") (pinfunction "IO23_37") (pintype "bidirectional"))
    )
    (net (code "66") (name "unconnected-(U4-IO32-Pad8)") (class "Default")
      (node (ref "U4") (pin "8") (pinfunction "IO32_8") (pintype "bidirectional"))
    )
    (net (code "67") (name "unconnected-(U4-IO34-Pad6)") (class "Default")
      (node (ref "U4") (pin "6") (pinfunction "IO34_6") (pintype "input"))
    )
    (net (code "68") (name "unconnected-(U4-IO35-Pad7)") (class "Default")
      (node (ref "U4") (pin "7") (pinfunction "IO35_7") (pintype "input"))
    )
    (net (code "69") (name "unconnected-(U4-NC-Pad32)") (class "Default")
      (node (ref "U4") (pin "32") (pinfunction "NC_32") (pintype "bidirectional"))
    )
    (net (code "70") (name "unconnected-(U4-SD1-Pad22)") (class "Default")
      (node (ref "U4") (pin "22") (pinfunction "SD1_22") (pintype "bidirectional"))
    )
    (net (code "71") (name "unconnected-(U4-SD2-Pad17)") (class "Default")
      (node (ref "U4") (pin "17") (pinfunction "SD2_17") (pintype "bidirectional"))
    )
    (net (code "72") (name "unconnected-(U4-SD3-Pad18)") (class "Default")
      (node (ref "U4") (pin "18") (pinfunction "SD3_18") (pintype "bidirectional"))
    )
    (net (code "73") (name "unconnected-(U4-SDO-Pad21)") (class "Default")
      (node (ref "U4") (pin "21") (pinfunction "SDO_21") (pintype "bidirectional"))
    )
    (net (code "74") (name "unconnected-(U4-SENSOR_VN-Pad5)") (class "Default")
      (node (ref "U4") (pin "5") (pinfunction "SENSOR_VN_5") (pintype "input"))
    )
    (net (code "75") (name "unconnected-(U4-SENSOR_VP-Pad4)") (class "Default")
      (node (ref "U4") (pin "4") (pinfunction "SENSOR_VP_4") (pintype "input"))
    )
  )
)
